# Control.net
KiCad netlist of a schematic drawn in Altium Designer
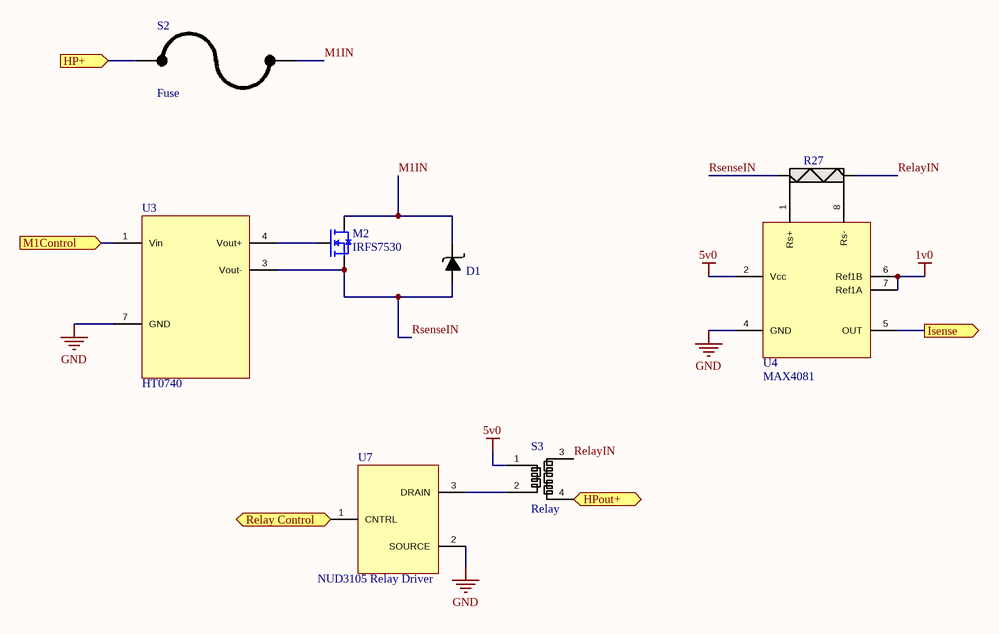
[diagram p0: Control.SchDoc]

(export (version "E")
  (design (tool "Eeschema 10.0.6"))
  (components
    (comp (ref "D1") (value "OR Diode") (footprint "POWERDI 5") (libsource (lib "SEM_BMS") (part "OR Diode")))
    (comp (ref "M2")
      (value "IRFS7530")
      (footprint "D2PAK-7")
      (description "IRFS7530 Power MOSFET")
      (libsource (lib "Components") (part "IRFS7530"))
    )
    (comp (ref "R27")
      (value "Isense Resistor")
      (footprint "SenseResistor")
      (libsource (lib "SEM_BMS") (part "Isense Resistor"))
    )
    (comp (ref "S2") (value "Fuse") (footprint "Fuse Holder") (libsource (lib "SEM_BMS") (part "Fuse")))
    (comp (ref "S3") (value "Relay") (footprint "JT-N Relay") (libsource (lib "SEM_BMS") (part "Relay")))
    (comp (ref "U3") (value "HT0740") (footprint "SOIC8") (libsource (lib "SEM_BMS") (part "HT0740")))
    (comp (ref "U4") (value "MAX4081") (footprint "SOIC8") (libsource (lib "Schlib1") (part "MAX4081")))
    (comp (ref "U7")
      (value "NUD3105 Relay Driver")
      (footprint "SOT23")
      (libsource (lib "SEM_BMS") (part "NUD3105 Relay Driver"))
    )
  )
  (nets
    (net (code "1") (name "/HP+") (class "Default") (node (ref "S2") (pin "1") (pintype "passive")))
    (net (code "2") (name "/HPout+") (class "Default")
      (node (ref "S3") (pin "4") (pinfunction "OUT2_4") (pintype "passive"))
    )
    (net (code "3") (name "/Isense") (class "Default")
      (node (ref "U4") (pin "5") (pinfunction "OUT_5") (pintype "passive"))
    )
    (net (code "4") (name "/M1Control") (class "Default")
      (node (ref "U3") (pin "1") (pinfunction "Vin_1") (pintype "passive"))
    )
    (net (code "5") (name "/M1IN") (class "Default")
      (node (ref "D1") (pin "2") (pinfunction "2_2") (pintype "passive"))
      (node (ref "M2") (pin "D") (pintype "passive"))
      (node (ref "S2") (pin "2") (pintype "passive"))
    )
    (net (code "6") (name "/Relay Control") (class "Default")
      (node (ref "U7") (pin "1") (pinfunction "CNTRL_1") (pintype "passive"))
    )
    (net (code "7") (name "/RelayIN") (class "Default")
      (node (ref "R27") (pin "2") (pinfunction "OUT_2") (pintype "passive"))
      (node (ref "S3") (pin "3") (pinfunction "OUT1_3") (pintype "passive"))
    )
    (net (code "8") (name "/RsenseIN") (class "Default")
      (node (ref "D1") (pin "1") (pintype "passive"))
      (node (ref "M2") (pin "S") (pintype "passive"))
      (node (ref "R27") (pin "1") (pinfunction "IN_1") (pintype "passive"))
      (node (ref "U3") (pin "3") (pinfunction "Vout-_3") (pintype "passive"))
    )
    (net (code "9") (name "1v0") (class "Default")
      (node (ref "U4") (pin "6") (pinfunction "Ref1B_6") (pintype "passive"))
      (node (ref "U4") (pin "7") (pinfunction "Ref1A_7") (pintype "passive"))
    )
    (net (code "10") (name "5v0") (class "Default")
      (node (ref "S3") (pin "1") (pinfunction "coil1_1") (pintype "passive"))
      (node (ref "U4") (pin "2") (pinfunction "Vcc_2") (pintype "passive"))
    )
    (net (code "11") (name "GND") (class "Default")
      (node (ref "U3") (pin "7") (pinfunction "GND_7") (pintype "passive"))
      (node (ref "U4") (pin "4") (pinfunction "GND_4") (pintype "passive"))
      (node (ref "U7") (pin "2") (pinfunction "SOURCE_2") (pintype "passive"))
    )
    (net (code "12") (name "Net-(R27-senseHI)") (class "Default")
      (node (ref "R27") (pin "3") (pinfunction "senseHI_3") (pintype "passive"))
      (node (ref "U4") (pin "1") (pinfunction "Rs+_1") (pintype "passive"))
    )
    (net (code "13") (name "Net-(R27-senseLOW)") (class "Default")
      (node (ref "R27") (pin "4") (pinfunction "senseLOW_4") (pintype "passive"))
      (node (ref "U4") (pin "8") (pinfunction "Rs-_8") (pintype "passive"))
    )
    (net (code "14") (name "Net-(S3-coil2)") (class "Default")
      (node (ref "S3") (pin "2") (pinfunction "coil2_2") (pintype "passive"))
      (node (ref "U7") (pin "3") (pinfunction "DRAIN_3") (pintype "passive"))
    )
    (net (code "15") (name "Net-(U3-Vout+)") (class "Default")
      (node (ref "M2") (pin "G") (pintype "passive"))
      (node (ref "U3") (pin "4") (pinfunction "Vout+_4") (pintype "passive"))
    )
  )
)
